# next_if_toy.net
KiCad netlist of a schematic drawn in EAGLE
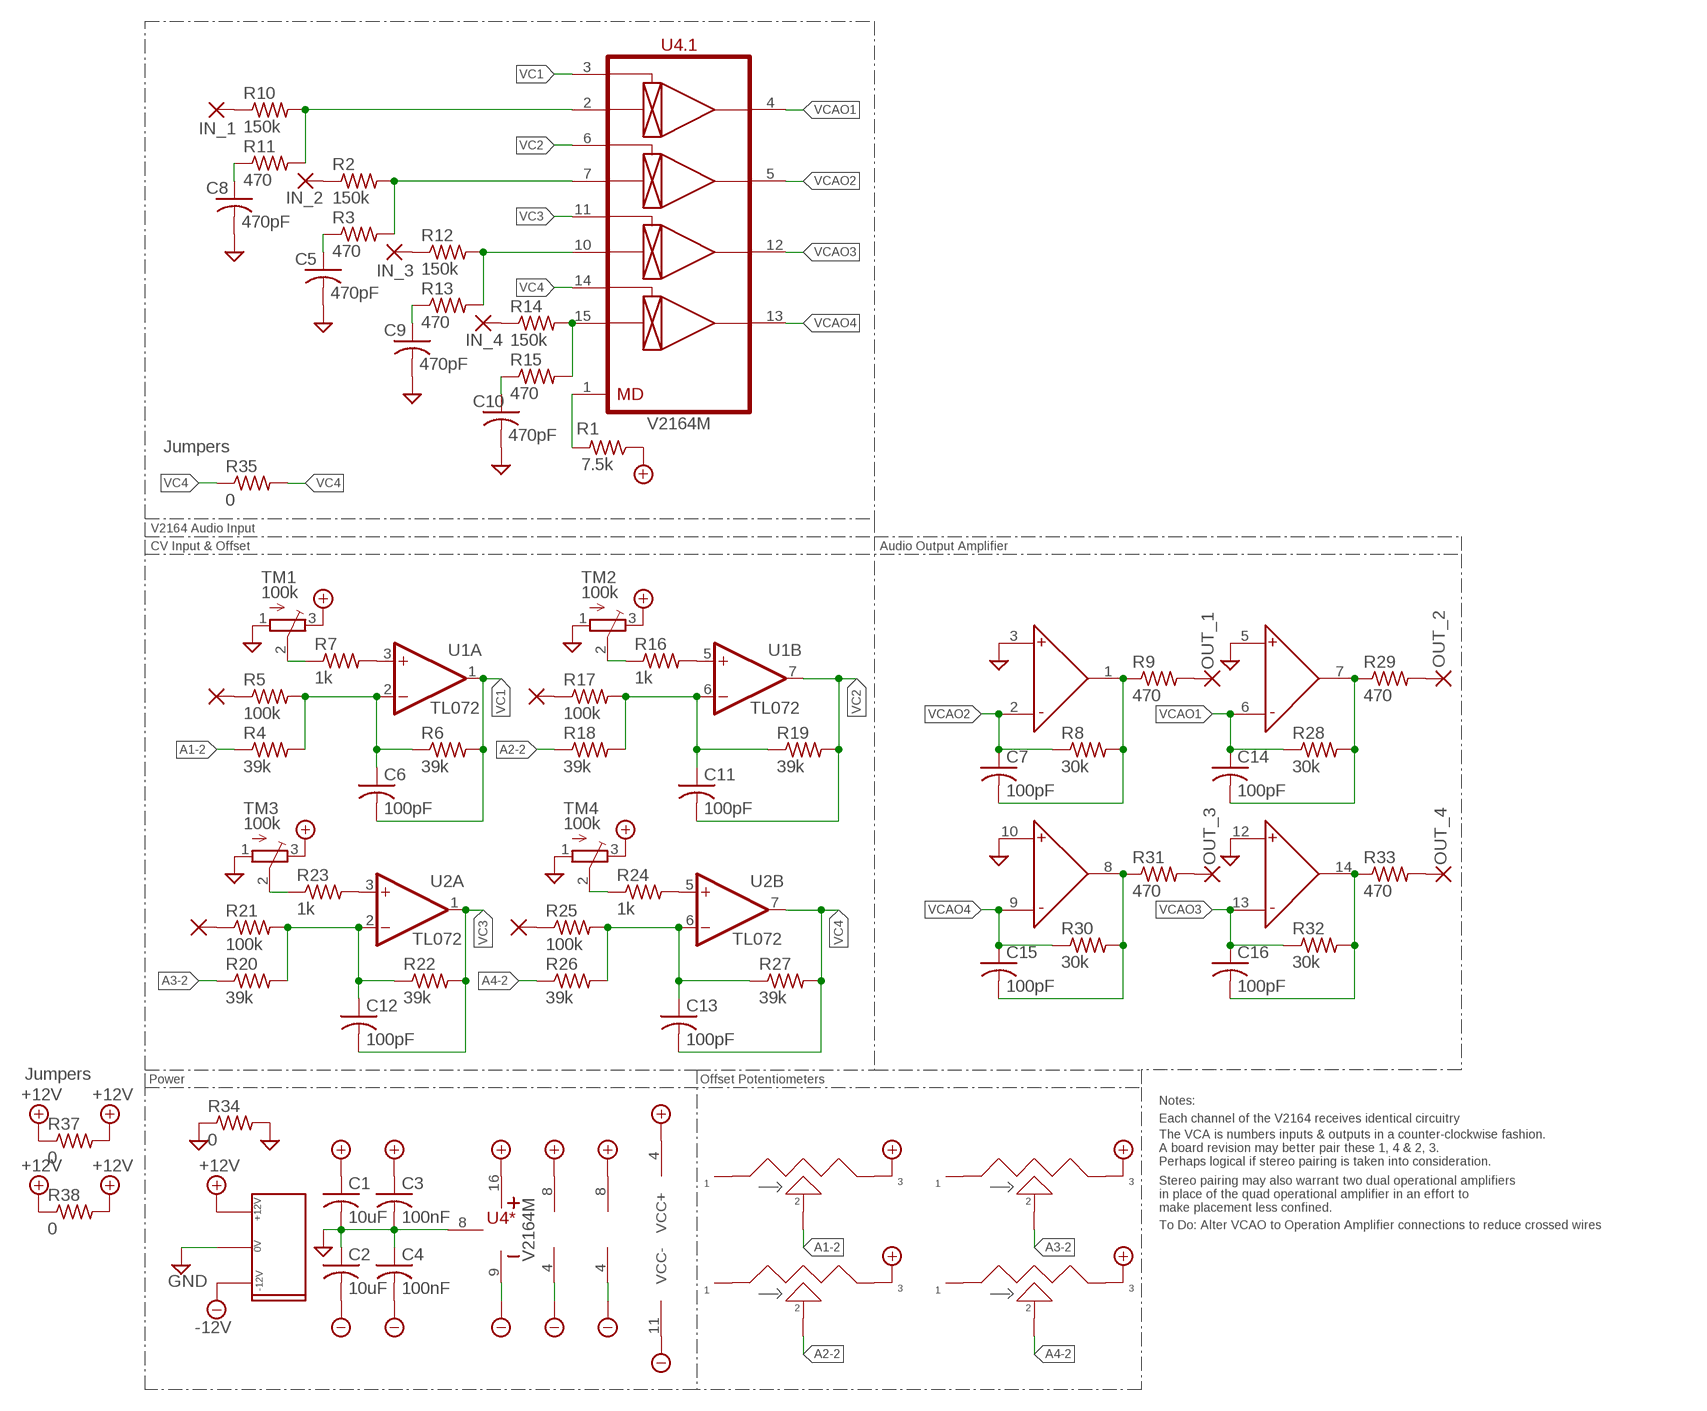
[diagram p0: schematic, sheet 1]

(export (version "E")
  (design (tool "Eeschema 10.0.6"))
  (components
    (comp (ref "AMT1")
      (value "B50k")
      (footprint "eagle-import:POT_9MM_SMD")
      (libsource (lib "eagle-import") (part "POT_9MM_SMD"))
    )
    (comp (ref "AMT2")
      (value "B50k")
      (footprint "eagle-import:POT_9MM_SMD")
      (libsource (lib "eagle-import") (part "POT_9MM_SMD"))
    )
    (comp (ref "AMT3")
      (value "B50k")
      (footprint "eagle-import:POT_9MM_SMD")
      (libsource (lib "eagle-import") (part "POT_9MM_SMD"))
    )
    (comp (ref "AMT4")
      (value "B50k")
      (footprint "eagle-import:POT_9MM_SMD")
      (libsource (lib "eagle-import") (part "POT_9MM_SMD"))
    )
    (comp (ref "C1")
      (value "10uF")
      (footprint "eagle-import:C1206")
      (libsource (lib "eagle-import") (part "C-USC1206"))
    )
    (comp (ref "C2")
      (value "10uF")
      (footprint "eagle-import:C1206")
      (libsource (lib "eagle-import") (part "C-USC1206"))
    )
    (comp (ref "C3")
      (value "100nF")
      (footprint "eagle-import:C0603")
      (libsource (lib "eagle-import") (part "C-USC0603"))
    )
    (comp (ref "C4")
      (value "100nF")
      (footprint "eagle-import:C0603")
      (libsource (lib "eagle-import") (part "C-USC0603"))
    )
    (comp (ref "C5")
      (value "470pF")
      (footprint "eagle-import:C0603")
      (libsource (lib "eagle-import") (part "C-USC0603"))
    )
    (comp (ref "C6")
      (value "100pF")
      (footprint "eagle-import:C0603")
      (libsource (lib "eagle-import") (part "C-USC0603"))
    )
    (comp (ref "C7")
      (value "100pF")
      (footprint "eagle-import:C0603")
      (libsource (lib "eagle-import") (part "C-USC0603"))
    )
    (comp (ref "C8")
      (value "470pF")
      (footprint "eagle-import:C0603")
      (libsource (lib "eagle-import") (part "C-USC0603"))
    )
    (comp (ref "C9")
      (value "470pF")
      (footprint "eagle-import:C0603")
      (libsource (lib "eagle-import") (part "C-USC0603"))
    )
    (comp (ref "C10")
      (value "470pF")
      (footprint "eagle-import:C0603")
      (libsource (lib "eagle-import") (part "C-USC0603"))
    )
    (comp (ref "C11")
      (value "100pF")
      (footprint "eagle-import:C0603")
      (libsource (lib "eagle-import") (part "C-USC0603"))
    )
    (comp (ref "C12")
      (value "100pF")
      (footprint "eagle-import:C0603")
      (libsource (lib "eagle-import") (part "C-USC0603"))
    )
    (comp (ref "C13")
      (value "100pF")
      (footprint "eagle-import:C0603")
      (libsource (lib "eagle-import") (part "C-USC0603"))
    )
    (comp (ref "C14")
      (value "100pF")
      (footprint "eagle-import:C0603")
      (libsource (lib "eagle-import") (part "C-USC0603"))
    )
    (comp (ref "C15")
      (value "100pF")
      (footprint "eagle-import:C0603")
      (libsource (lib "eagle-import") (part "C-USC0603"))
    )
    (comp (ref "C16")
      (value "100pF")
      (footprint "eagle-import:C0603")
      (libsource (lib "eagle-import") (part "C-USC0603"))
    )
    (comp (ref "CV1")
      (value "SMD2")
      (footprint "eagle-import:SMD1,27-2,54")
      (libsource (lib "eagle-import") (part "SMD2"))
    )
    (comp (ref "CV2")
      (value "SMD2")
      (footprint "eagle-import:SMD1,27-2,54")
      (libsource (lib "eagle-import") (part "SMD2"))
    )
    (comp (ref "CV3")
      (value "SMD2")
      (footprint "eagle-import:SMD1,27-2,54")
      (libsource (lib "eagle-import") (part "SMD2"))
    )
    (comp (ref "CV4")
      (value "SMD2")
      (footprint "eagle-import:SMD1,27-2,54")
      (libsource (lib "eagle-import") (part "SMD2"))
    )
    (comp (ref "I1")
      (value "SMD2")
      (footprint "eagle-import:SMD1,27-2,54")
      (libsource (lib "eagle-import") (part "SMD2"))
    )
    (comp (ref "I2")
      (value "SMD2")
      (footprint "eagle-import:SMD1,27-2,54")
      (libsource (lib "eagle-import") (part "SMD2"))
    )
    (comp (ref "I3")
      (value "SMD2")
      (footprint "eagle-import:SMD1,27-2,54")
      (libsource (lib "eagle-import") (part "SMD2"))
    )
    (comp (ref "I4")
      (value "SMD2")
      (footprint "eagle-import:SMD1,27-2,54")
      (libsource (lib "eagle-import") (part "SMD2"))
    )
    (comp (ref "O1")
      (value "SMD2")
      (footprint "eagle-import:SMD1,27-2,54")
      (libsource (lib "eagle-import") (part "SMD2"))
    )
    (comp (ref "O2")
      (value "SMD2")
      (footprint "eagle-import:SMD1,27-2,54")
      (libsource (lib "eagle-import") (part "SMD2"))
    )
    (comp (ref "O3")
      (value "SMD2")
      (footprint "eagle-import:SMD1,27-2,54")
      (libsource (lib "eagle-import") (part "SMD2"))
    )
    (comp (ref "O4")
      (value "SMD2")
      (footprint "eagle-import:SMD1,27-2,54")
      (libsource (lib "eagle-import") (part "SMD2"))
    )
    (comp (ref "R1")
      (value "7.5k")
      (footprint "eagle-import:R0603")
      (libsource (lib "eagle-import") (part "R-US_R0603"))
    )
    (comp (ref "R2")
      (value "150k")
      (footprint "eagle-import:R0603")
      (libsource (lib "eagle-import") (part "R-US_R0603"))
    )
    (comp (ref "R3")
      (value "470")
      (footprint "eagle-import:R0603")
      (libsource (lib "eagle-import") (part "R-US_R0603"))
    )
    (comp (ref "R4")
      (value "39k")
      (footprint "eagle-import:R0603")
      (libsource (lib "eagle-import") (part "R-US_R0603"))
    )
    (comp (ref "R5")
      (value "100k")
      (footprint "eagle-import:R0603")
      (libsource (lib "eagle-import") (part "R-US_R0603"))
    )
    (comp (ref "R6")
      (value "39k")
      (footprint "eagle-import:R0603")
      (libsource (lib "eagle-import") (part "R-US_R0603"))
    )
    (comp (ref "R7")
      (value "1k")
      (footprint "eagle-import:R0603")
      (libsource (lib "eagle-import") (part "R-US_R0603"))
    )
    (comp (ref "R8")
      (value "30k")
      (footprint "eagle-import:R0603")
      (libsource (lib "eagle-import") (part "R-US_R0603"))
    )
    (comp (ref "R9")
      (value "470")
      (footprint "eagle-import:R0603")
      (libsource (lib "eagle-import") (part "R-US_R0603"))
    )
    (comp (ref "R10")
      (value "150k")
      (footprint "eagle-import:R0603")
      (libsource (lib "eagle-import") (part "R-US_R0603"))
    )
    (comp (ref "R11")
      (value "470")
      (footprint "eagle-import:R0603")
      (libsource (lib "eagle-import") (part "R-US_R0603"))
    )
    (comp (ref "R12")
      (value "150k")
      (footprint "eagle-import:R0603")
      (libsource (lib "eagle-import") (part "R-US_R0603"))
    )
    (comp (ref "R13")
      (value "470")
      (footprint "eagle-import:R0603")
      (libsource (lib "eagle-import") (part "R-US_R0603"))
    )
    (comp (ref "R14")
      (value "150k")
      (footprint "eagle-import:R0603")
      (libsource (lib "eagle-import") (part "R-US_R0603"))
    )
    (comp (ref "R15")
      (value "470")
      (footprint "eagle-import:R0603")
      (libsource (lib "eagle-import") (part "R-US_R0603"))
    )
    (comp (ref "R16")
      (value "1k")
      (footprint "eagle-import:R0603")
      (libsource (lib "eagle-import") (part "R-US_R0603"))
    )
    (comp (ref "R17")
      (value "100k")
      (footprint "eagle-import:R0603")
      (libsource (lib "eagle-import") (part "R-US_R0603"))
    )
    (comp (ref "R18")
      (value "39k")
      (footprint "eagle-import:R0603")
      (libsource (lib "eagle-import") (part "R-US_R0603"))
    )
    (comp (ref "R19")
      (value "39k")
      (footprint "eagle-import:R0603")
      (libsource (lib "eagle-import") (part "R-US_R0603"))
    )
    (comp (ref "R20")
      (value "39k")
      (footprint "eagle-import:R0603")
      (libsource (lib "eagle-import") (part "R-US_R0603"))
    )
    (comp (ref "R21")
      (value "100k")
      (footprint "eagle-import:R0603")
      (libsource (lib "eagle-import") (part "R-US_R0603"))
    )
    (comp (ref "R22")
      (value "39k")
      (footprint "eagle-import:R0603")
      (libsource (lib "eagle-import") (part "R-US_R0603"))
    )
    (comp (ref "R23")
      (value "1k")
      (footprint "eagle-import:R0603")
      (libsource (lib "eagle-import") (part "R-US_R0603"))
    )
    (comp (ref "R24")
      (value "1k")
      (footprint "eagle-import:R0603")
      (libsource (lib "eagle-import") (part "R-US_R0603"))
    )
    (comp (ref "R25")
      (value "100k")
      (footprint "eagle-import:R0603")
      (libsource (lib "eagle-import") (part "R-US_R0603"))
    )
    (comp (ref "R26")
      (value "39k")
      (footprint "eagle-import:R0603")
      (libsource (lib "eagle-import") (part "R-US_R0603"))
    )
    (comp (ref "R27")
      (value "39k")
      (footprint "eagle-import:R0603")
      (libsource (lib "eagle-import") (part "R-US_R0603"))
    )
    (comp (ref "R28")
      (value "30k")
      (footprint "eagle-import:R0603")
      (libsource (lib "eagle-import") (part "R-US_R0603"))
    )
    (comp (ref "R29")
      (value "470")
      (footprint "eagle-import:R0603")
      (libsource (lib "eagle-import") (part "R-US_R0603"))
    )
    (comp (ref "R30")
      (value "30k")
      (footprint "eagle-import:R0603")
      (libsource (lib "eagle-import") (part "R-US_R0603"))
    )
    (comp (ref "R31")
      (value "470")
      (footprint "eagle-import:R0603")
      (libsource (lib "eagle-import") (part "R-US_R0603"))
    )
    (comp (ref "R32")
      (value "30k")
      (footprint "eagle-import:R0603")
      (libsource (lib "eagle-import") (part "R-US_R0603"))
    )
    (comp (ref "R33")
      (value "470")
      (footprint "eagle-import:R0603")
      (libsource (lib "eagle-import") (part "R-US_R0603"))
    )
    (comp (ref "R34")
      (value "0")
      (footprint "eagle-import:R0402")
      (libsource (lib "eagle-import") (part "R-US_R0402"))
    )
    (comp (ref "R35")
      (value "0")
      (footprint "eagle-import:R0402")
      (libsource (lib "eagle-import") (part "R-US_R0402"))
    )
    (comp (ref "R37")
      (value "0")
      (footprint "eagle-import:R0402")
      (libsource (lib "eagle-import") (part "R-US_R0402"))
    )
    (comp (ref "R38")
      (value "0")
      (footprint "eagle-import:R0402")
      (libsource (lib "eagle-import") (part "R-US_R0402"))
    )
    (comp (ref "TM1")
      (value "100k")
      (footprint "eagle-import:TC33X")
      (libsource (lib "eagle-import") (part "TRIMPOTTC33X"))
    )
    (comp (ref "TM2")
      (value "100k")
      (footprint "eagle-import:TC33X")
      (libsource (lib "eagle-import") (part "TRIMPOTTC33X"))
    )
    (comp (ref "TM3")
      (value "100k")
      (footprint "eagle-import:TC33X")
      (libsource (lib "eagle-import") (part "TRIMPOTTC33X"))
    )
    (comp (ref "TM4")
      (value "100k")
      (footprint "eagle-import:TC33X")
      (libsource (lib "eagle-import") (part "TRIMPOTTC33X"))
    )
    (comp (ref "U$2")
      (value "EURO_POW_CEH")
      (footprint "eagle-import:EURO_POW_CEH")
      (libsource (lib "eagle-import") (part "EURO_POW_CEH"))
    )
    (comp (ref "U1")
      (value "TL072")
      (footprint "eagle-import:TSSOP-8")
      (libsource (lib "eagle-import") (part "TL072TSSOP"))
    )
    (comp (ref "U2")
      (value "TL072")
      (footprint "eagle-import:TSSOP-8")
      (libsource (lib "eagle-import") (part "TL072TSSOP"))
    )
    (comp (ref "U3")
      (value "TL074TSSOP-14")
      (footprint "eagle-import:TL074TSSOP-14")
      (libsource (lib "eagle-import") (part "TL074TSSOP-14"))
    )
    (comp (ref "U4")
      (value "V2164M")
      (footprint "eagle-import:SO-16")
      (libsource (lib "eagle-import") (part "V2164M"))
    )
  )
  (nets
    (net (code "1") (name "+12V") (class "Default")
      (node (ref "AMT1") (pin "3") (pinfunction "3_3") (pintype "bidirectional"))
      (node (ref "AMT2") (pin "3") (pinfunction "3_3") (pintype "bidirectional"))
      (node (ref "AMT3") (pin "3") (pinfunction "3_3") (pintype "bidirectional"))
      (node (ref "AMT4") (pin "3") (pinfunction "3_3") (pintype "bidirectional"))
      (node (ref "C1") (pin "1") (pinfunction "1_1") (pintype "passive"))
      (node (ref "C3") (pin "1") (pinfunction "1_1") (pintype "passive"))
      (node (ref "R1") (pin "1") (pinfunction "1_1") (pintype "passive"))
      (node (ref "R37") (pin "1") (pinfunction "1_1") (pintype "passive"))
      (node (ref "R37") (pin "2") (pinfunction "2_2") (pintype "passive"))
      (node (ref "R38") (pin "1") (pinfunction "1_1") (pintype "passive"))
      (node (ref "R38") (pin "2") (pinfunction "2_2") (pintype "passive"))
      (node (ref "TM1") (pin "3") (pinfunction "E_3") (pintype "passive"))
      (node (ref "TM2") (pin "3") (pinfunction "E_3") (pintype "passive"))
      (node (ref "TM3") (pin "3") (pinfunction "E_3") (pintype "passive"))
      (node (ref "TM4") (pin "3") (pinfunction "E_3") (pintype "passive"))
      (node (ref "U$2") (pin "+12V") (pinfunction "+12V_+12V") (pintype "bidirectional"))
      (node (ref "U1") (pin "8") (pinfunction "V+_8") (pintype "power_in"))
      (node (ref "U2") (pin "8") (pinfunction "V+_8") (pintype "power_in"))
      (node (ref "U3") (pin "4") (pinfunction "VCC+_4") (pintype "power_in"))
      (node (ref "U4") (pin "16") (pinfunction "V+_16") (pintype "power_in"))
    )
    (net (code "2") (name "-12V") (class "Default")
      (node (ref "C2") (pin "2") (pinfunction "2_2") (pintype "passive"))
      (node (ref "C4") (pin "2") (pinfunction "2_2") (pintype "passive"))
      (node (ref "U$2") (pin "-12V") (pinfunction "-12V_-12V") (pintype "bidirectional"))
      (node (ref "U1") (pin "4") (pinfunction "V-_4") (pintype "power_in"))
      (node (ref "U2") (pin "4") (pinfunction "V-_4") (pintype "power_in"))
      (node (ref "U3") (pin "11") (pinfunction "VCC-_11") (pintype "power_in"))
      (node (ref "U4") (pin "9") (pinfunction "V-_9") (pintype "power_in"))
    )
    (net (code "3") (name "A1-2") (class "Default")
      (node (ref "AMT1") (pin "2") (pinfunction "2_2") (pintype "bidirectional"))
      (node (ref "R4") (pin "1") (pinfunction "1_1") (pintype "passive"))
    )
    (net (code "4") (name "A2-2") (class "Default")
      (node (ref "AMT2") (pin "2") (pinfunction "2_2") (pintype "bidirectional"))
      (node (ref "R18") (pin "1") (pinfunction "1_1") (pintype "passive"))
    )
    (net (code "5") (name "A3-2") (class "Default")
      (node (ref "AMT3") (pin "2") (pinfunction "2_2") (pintype "bidirectional"))
      (node (ref "R20") (pin "1") (pinfunction "1_1") (pintype "passive"))
    )
    (net (code "6") (name "A4-2") (class "Default")
      (node (ref "AMT4") (pin "2") (pinfunction "2_2") (pintype "bidirectional"))
      (node (ref "R26") (pin "1") (pinfunction "1_1") (pintype "passive"))
    )
    (net (code "7") (name "GND") (class "Default")
      (node (ref "C1") (pin "2") (pinfunction "2_2") (pintype "passive"))
      (node (ref "C10") (pin "2") (pinfunction "2_2") (pintype "passive"))
      (node (ref "C2") (pin "1") (pinfunction "1_1") (pintype "passive"))
      (node (ref "C3") (pin "2") (pinfunction "2_2") (pintype "passive"))
      (node (ref "C4") (pin "1") (pinfunction "1_1") (pintype "passive"))
      (node (ref "C5") (pin "2") (pinfunction "2_2") (pintype "passive"))
      (node (ref "C8") (pin "2") (pinfunction "2_2") (pintype "passive"))
      (node (ref "C9") (pin "2") (pinfunction "2_2") (pintype "passive"))
      (node (ref "R34") (pin "1") (pinfunction "1_1") (pintype "passive"))
      (node (ref "R34") (pin "2") (pinfunction "2_2") (pintype "passive"))
      (node (ref "TM1") (pin "1") (pinfunction "A_1") (pintype "passive"))
      (node (ref "TM2") (pin "1") (pinfunction "A_1") (pintype "passive"))
      (node (ref "TM3") (pin "1") (pinfunction "A_1") (pintype "passive"))
      (node (ref "TM4") (pin "1") (pinfunction "A_1") (pintype "passive"))
      (node (ref "U$2") (pin "GND") (pinfunction "GND_GND") (pintype "bidirectional"))
      (node (ref "U3") (pin "10") (pinfunction "I+_10") (pintype "bidirectional"))
      (node (ref "U3") (pin "12") (pinfunction "I+_12") (pintype "bidirectional"))
      (node (ref "U3") (pin "3") (pinfunction "I+_3") (pintype "bidirectional"))
      (node (ref "U3") (pin "5") (pinfunction "I+_5") (pintype "bidirectional"))
      (node (ref "U4") (pin "8") (pinfunction "GND_8") (pintype "power_in"))
    )
    (net (code "8") (name "Net-(C5-Pad1)") (class "Default")
      (node (ref "C5") (pin "1") (pinfunction "1_1") (pintype "passive"))
      (node (ref "R3") (pin "1") (pinfunction "1_1") (pintype "passive"))
    )
    (net (code "9") (name "Net-(C8-Pad1)") (class "Default")
      (node (ref "C8") (pin "1") (pinfunction "1_1") (pintype "passive"))
      (node (ref "R11") (pin "1") (pinfunction "1_1") (pintype "passive"))
    )
    (net (code "10") (name "Net-(C9-Pad1)") (class "Default")
      (node (ref "C9") (pin "1") (pinfunction "1_1") (pintype "passive"))
      (node (ref "R13") (pin "1") (pinfunction "1_1") (pintype "passive"))
    )
    (net (code "11") (name "Net-(C10-Pad1)") (class "Default")
      (node (ref "C10") (pin "1") (pinfunction "1_1") (pintype "passive"))
      (node (ref "R15") (pin "1") (pinfunction "1_1") (pintype "passive"))
    )
    (net (code "12") (name "Net-(CV1-P)") (class "Default")
      (node (ref "CV1") (pin "1") (pinfunction "P_1") (pintype "passive"))
      (node (ref "R5") (pin "1") (pinfunction "1_1") (pintype "passive"))
    )
    (net (code "13") (name "Net-(CV2-P)") (class "Default")
      (node (ref "CV2") (pin "1") (pinfunction "P_1") (pintype "passive"))
      (node (ref "R17") (pin "1") (pinfunction "1_1") (pintype "passive"))
    )
    (net (code "14") (name "Net-(CV3-P)") (class "Default")
      (node (ref "CV3") (pin "1") (pinfunction "P_1") (pintype "passive"))
      (node (ref "R21") (pin "1") (pinfunction "1_1") (pintype "passive"))
    )
    (net (code "15") (name "Net-(CV4-P)") (class "Default")
      (node (ref "CV4") (pin "1") (pinfunction "P_1") (pintype "passive"))
      (node (ref "R25") (pin "1") (pinfunction "1_1") (pintype "passive"))
    )
    (net (code "16") (name "Net-(I1-P)") (class "Default")
      (node (ref "I1") (pin "1") (pinfunction "P_1") (pintype "passive"))
      (node (ref "R10") (pin "1") (pinfunction "1_1") (pintype "passive"))
    )
    (net (code "17") (name "Net-(I2-P)") (class "Default")
      (node (ref "I2") (pin "1") (pinfunction "P_1") (pintype "passive"))
      (node (ref "R2") (pin "1") (pinfunction "1_1") (pintype "passive"))
    )
    (net (code "18") (name "Net-(I3-P)") (class "Default")
      (node (ref "I3") (pin "1") (pinfunction "P_1") (pintype "passive"))
      (node (ref "R12") (pin "1") (pinfunction "1_1") (pintype "passive"))
    )
    (net (code "19") (name "Net-(I4-P)") (class "Default")
      (node (ref "I4") (pin "1") (pinfunction "P_1") (pintype "passive"))
      (node (ref "R14") (pin "1") (pinfunction "1_1") (pintype "passive"))
    )
    (net (code "20") (name "Net-(O1-P)") (class "Default")
      (node (ref "O1") (pin "1") (pinfunction "P_1") (pintype "passive"))
      (node (ref "R9") (pin "2") (pinfunction "2_2") (pintype "passive"))
    )
    (net (code "21") (name "Net-(O2-P)") (class "Default")
      (node (ref "O2") (pin "1") (pinfunction "P_1") (pintype "passive"))
      (node (ref "R29") (pin "2") (pinfunction "2_2") (pintype "passive"))
    )
    (net (code "22") (name "Net-(O3-P)") (class "Default")
      (node (ref "O3") (pin "1") (pinfunction "P_1") (pintype "passive"))
      (node (ref "R31") (pin "2") (pinfunction "2_2") (pintype "passive"))
    )
    (net (code "23") (name "Net-(O4-P)") (class "Default")
      (node (ref "O4") (pin "1") (pinfunction "P_1") (pintype "passive"))
      (node (ref "R33") (pin "2") (pinfunction "2_2") (pintype "passive"))
    )
    (net (code "24") (name "Net-(TM1-S)") (class "Default")
      (node (ref "R7") (pin "1") (pinfunction "1_1") (pintype "passive"))
      (node (ref "TM1") (pin "2") (pinfunction "S_2") (pintype "passive"))
    )
    (net (code "25") (name "Net-(TM2-S)") (class "Default")
      (node (ref "R16") (pin "1") (pinfunction "1_1") (pintype "passive"))
      (node (ref "TM2") (pin "2") (pinfunction "S_2") (pintype "passive"))
    )
    (net (code "26") (name "Net-(TM3-S)") (class "Default")
      (node (ref "R23") (pin "1") (pinfunction "1_1") (pintype "passive"))
      (node (ref "TM3") (pin "2") (pinfunction "S_2") (pintype "passive"))
    )
    (net (code "27") (name "Net-(TM4-S)") (class "Default")
      (node (ref "R24") (pin "1") (pinfunction "1_1") (pintype "passive"))
      (node (ref "TM4") (pin "2") (pinfunction "S_2") (pintype "passive"))
    )
    (net (code "28") (name "Net-(U1A-+IN)") (class "Default")
      (node (ref "R7") (pin "2") (pinfunction "2_2") (pintype "passive"))
      (node (ref "U1") (pin "3") (pinfunction "+IN_3") (pintype "input"))
    )
    (net (code "29") (name "Net-(U1A--IN)") (class "Default")
      (node (ref "C6") (pin "1") (pinfunction "1_1") (pintype "passive"))
      (node (ref "R4") (pin "2") (pinfunction "2_2") (pintype "passive"))
      (node (ref "R5") (pin "2") (pinfunction "2_2") (pintype "passive"))
      (node (ref "R6") (pin "1") (pinfunction "1_1") (pintype "passive"))
      (node (ref "U1") (pin "2") (pinfunction "-IN_2") (pintype "input"))
    )
    (net (code "30") (name "Net-(U1B-+IN)") (class "Default")
      (node (ref "R16") (pin "2") (pinfunction "2_2") (pintype "passive"))
      (node (ref "U1") (pin "5") (pinfunction "+IN_5") (pintype "input"))
    )
    (net (code "31") (name "Net-(U1B--IN)") (class "Default")
      (node (ref "C11") (pin "1") (pinfunction "1_1") (pintype "passive"))
      (node (ref "R17") (pin "2") (pinfunction "2_2") (pintype "passive"))
      (node (ref "R18") (pin "2") (pinfunction "2_2") (pintype "passive"))
      (node (ref "R19") (pin "1") (pinfunction "1_1") (pintype "passive"))
      (node (ref "U1") (pin "6") (pinfunction "-IN_6") (pintype "input"))
    )
    (net (code "32") (name "Net-(U2A-+IN)") (class "Default")
      (node (ref "R23") (pin "2") (pinfunction "2_2") (pintype "passive"))
      (node (ref "U2") (pin "3") (pinfunction "+IN_3") (pintype "input"))
    )
    (net (code "33") (name "Net-(U2A--IN)") (class "Default")
      (node (ref "C12") (pin "1") (pinfunction "1_1") (pintype "passive"))
      (node (ref "R20") (pin "2") (pinfunction "2_2") (pintype "passive"))
      (node (ref "R21") (pin "2") (pinfunction "2_2") (pintype "passive"))
      (node (ref "R22") (pin "1") (pinfunction "1_1") (pintype "passive"))
      (node (ref "U2") (pin "2") (pinfunction "-IN_2") (pintype "input"))
    )
    (net (code "34") (name "Net-(U2B-+IN)") (class "Default")
      (node (ref "R24") (pin "2") (pinfunction "2_2") (pintype "passive"))
      (node (ref "U2") (pin "5") (pinfunction "+IN_5") (pintype "input"))
    )
    (net (code "35") (name "Net-(U2B--IN)") (class "Default")
      (node (ref "C13") (pin "1") (pinfunction "1_1") (pintype "passive"))
      (node (ref "R25") (pin "2") (pinfunction "2_2") (pintype "passive"))
      (node (ref "R26") (pin "2") (pinfunction "2_2") (pintype "passive"))
      (node (ref "R27") (pin "1") (pinfunction "1_1") (pintype "passive"))
      (node (ref "U2") (pin "6") (pinfunction "-IN_6") (pintype "input"))
    )
    (net (code "36") (name "Net-(U3A-O)") (class "Default")
      (node (ref "C7") (pin "2") (pinfunction "2_2") (pintype "passive"))
      (node (ref "R8") (pin "2") (pinfunction "2_2") (pintype "passive"))
      (node (ref "R9") (pin "1") (pinfunction "1_1") (pintype "passive"))
      (node (ref "U3") (pin "1") (pinfunction "O_1") (pintype "bidirectional"))
    )
    (net (code "37") (name "Net-(U3B-O)") (class "Default")
      (node (ref "C14") (pin "2") (pinfunction "2_2") (pintype "passive"))
      (node (ref "R28") (pin "2") (pinfunction "2_2") (pintype "passive"))
      (node (ref "R29") (pin "1") (pinfunction "1_1") (pintype "passive"))
      (node (ref "U3") (pin "7") (pinfunction "O_7") (pintype "bidirectional"))
    )
    (net (code "38") (name "Net-(U3C-O)") (class "Default")
      (node (ref "C15") (pin "2") (pinfunction "2_2") (pintype "passive"))
      (node (ref "R30") (pin "2") (pinfunction "2_2") (pintype "passive"))
      (node (ref "R31") (pin "1") (pinfunction "1_1") (pintype "passive"))
      (node (ref "U3") (pin "8") (pinfunction "O_8") (pintype "bidirectional"))
    )
    (net (code "39") (name "Net-(U3D-O)") (class "Default")
      (node (ref "C16") (pin "2") (pinfunction "2_2") (pintype "passive"))
      (node (ref "R32") (pin "2") (pinfunction "2_2") (pintype "passive"))
      (node (ref "R33") (pin "1") (pinfunction "1_1") (pintype "passive"))
      (node (ref "U3") (pin "14") (pinfunction "O_14") (pintype "bidirectional"))
    )
    (net (code "40") (name "Net-(U4B-IN1)") (class "Default")
      (node (ref "R10") (pin "2") (pinfunction "2_2") (pintype "passive"))
      (node (ref "R11") (pin "2") (pinfunction "2_2") (pintype "passive"))
      (node (ref "U4") (pin "2") (pinfunction "IN1_2") (pintype "input"))
    )
    (net (code "41") (name "Net-(U4B-IN2)") (class "Default")
      (node (ref "R2") (pin "2") (pinfunction "2_2") (pintype "passive"))
      (node (ref "R3") (pin "2") (pinfunction "2_2") (pintype "passive"))
      (node (ref "U4") (pin "7") (pinfunction "IN2_7") (pintype "input"))
    )
    (net (code "42") (name "Net-(U4B-IN3)") (class "Default")
      (node (ref "R12") (pin "2") (pinfunction "2_2") (pintype "passive"))
      (node (ref "R13") (pin "2") (pinfunction "2_2") (pintype "passive"))
      (node (ref "U4") (pin "10") (pinfunction "IN3_10") (pintype "input"))
    )
    (net (code "43") (name "Net-(U4B-IN4)") (class "Default")
      (node (ref "R14") (pin "2") (pinfunction "2_2") (pintype "passive"))
      (node (ref "R15") (pin "2") (pinfunction "2_2") (pintype "passive"))
      (node (ref "U4") (pin "15") (pinfunction "IN4_15") (pintype "input"))
    )
    (net (code "44") (name "Net-(U4B-MD)") (class "Default")
      (node (ref "R1") (pin "2") (pinfunction "2_2") (pintype "passive"))
      (node (ref "U4") (pin "1") (pinfunction "MD_1") (pintype "output"))
    )
    (net (code "45") (name "VC1") (class "Default")
      (node (ref "C6") (pin "2") (pinfunction "2_2") (pintype "passive"))
      (node (ref "R6") (pin "2") (pinfunction "2_2") (pintype "passive"))
      (node (ref "U1") (pin "1") (pinfunction "OUT_1") (pintype "output"))
      (node (ref "U4") (pin "3") (pinfunction "CV1_3") (pintype "input"))
    )
    (net (code "46") (name "VC2") (class "Default")
      (node (ref "C11") (pin "2") (pinfunction "2_2") (pintype "passive"))
      (node (ref "R19") (pin "2") (pinfunction "2_2") (pintype "passive"))
      (node (ref "U1") (pin "7") (pinfunction "OUT_7") (pintype "output"))
      (node (ref "U4") (pin "6") (pinfunction "CV2_6") (pintype "input"))
    )
    (net (code "47") (name "VC3") (class "Default")
      (node (ref "C12") (pin "2") (pinfunction "2_2") (pintype "passive"))
      (node (ref "R22") (pin "2") (pinfunction "2_2") (pintype "passive"))
      (node (ref "U2") (pin "1") (pinfunction "OUT_1") (pintype "output"))
      (node (ref "U4") (pin "11") (pinfunction "CV3_11") (pintype "input"))
    )
    (net (code "48") (name "VC4") (class "Default")
      (node (ref "C13") (pin "2") (pinfunction "2_2") (pintype "passive"))
      (node (ref "R27") (pin "2") (pinfunction "2_2") (pintype "passive"))
      (node (ref "R35") (pin "1") (pinfunction "1_1") (pintype "passive"))
      (node (ref "R35") (pin "2") (pinfunction "2_2") (pintype "passive"))
      (node (ref "U2") (pin "7") (pinfunction "OUT_7") (pintype "output"))
      (node (ref "U4") (pin "14") (pinfunction "CV4_14") (pintype "input"))
    )
    (net (code "49") (name "VCAO1") (class "Default")
      (node (ref "C14") (pin "1") (pinfunction "1_1") (pintype "passive"))
      (node (ref "R28") (pin "1") (pinfunction "1_1") (pintype "passive"))
      (node (ref "U3") (pin "6") (pinfunction "I-_6") (pintype "bidirectional"))
      (node (ref "U4") (pin "4") (pinfunction "OUT1_4") (pintype "output"))
    )
    (net (code "50") (name "VCAO2") (class "Default")
      (node (ref "C7") (pin "1") (pinfunction "1_1") (pintype "passive"))
      (node (ref "R8") (pin "1") (pinfunction "1_1") (pintype "passive"))
      (node (ref "U3") (pin "2") (pinfunction "I-_2") (pintype "bidirectional"))
      (node (ref "U4") (pin "5") (pinfunction "OUT2_5") (pintype "output"))
    )
    (net (code "51") (name "VCAO3") (class "Default")
      (node (ref "C16") (pin "1") (pinfunction "1_1") (pintype "passive"))
      (node (ref "R32") (pin "1") (pinfunction "1_1") (pintype "passive"))
      (node (ref "U3") (pin "13") (pinfunction "I-_13") (pintype "bidirectional"))
      (node (ref "U4") (pin "12") (pinfunction "OUT3_12") (pintype "output"))
    )
    (net (code "52") (name "VCAO4") (class "Default")
      (node (ref "C15") (pin "1") (pinfunction "1_1") (pintype "passive"))
      (node (ref "R30") (pin "1") (pinfunction "1_1") (pintype "passive"))
      (node (ref "U3") (pin "9") (pinfunction "I-_9") (pintype "bidirectional"))
      (node (ref "U4") (pin "13") (pinfunction "OUT4_13") (pintype "output"))
    )
    (net (code "53") (name "unconnected-(AMT1-Pad1)") (class "Default")
      (node (ref "AMT1") (pin "1") (pinfunction "1_1") (pintype "bidirectional"))
    )
    (net (code "54") (name "unconnected-(AMT2-Pad1)") (class "Default")
      (node (ref "AMT2") (pin "1") (pinfunction "1_1") (pintype "bidirectional"))
    )
    (net (code "55") (name "unconnected-(AMT3-Pad1)") (class "Default")
      (node (ref "AMT3") (pin "1") (pinfunction "1_1") (pintype "bidirectional"))
    )
    (net (code "56") (name "unconnected-(AMT4-Pad1)") (class "Default")
      (node (ref "AMT4") (pin "1") (pinfunction "1_1") (pintype "bidirectional"))
    )
  )
)
